# Redundant_Power_Supplies.net
KiCad netlist of a schematic drawn in Altium Designer
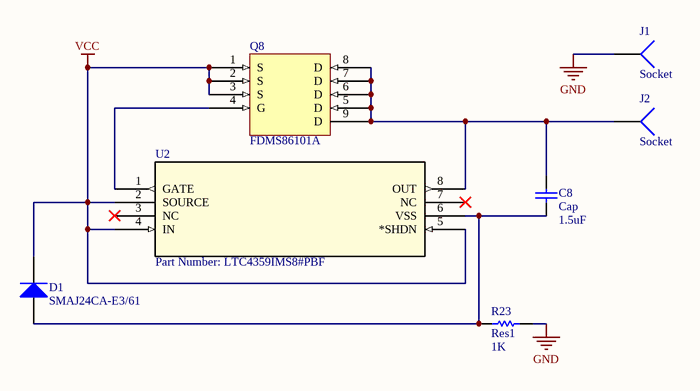
[diagram p0: Redundant Power Supplies.SchDoc]

(export (version "E")
  (design (tool "Eeschema 10.0.6"))
  (components
    (comp (ref "C8")
      (value "Cap")
      (footprint "C2012X7R1A155K:CAP_2012")
      (description "Capacitor")
      (fields (field (name "ALTIUM_VALUE") "1.5uF") (field (name "PUBLISHER") "Altium Limited"))
      (libsource (lib "Miscellaneous Devices") (part "Cap"))
    )
    (comp (ref "D1")
      (value "SMAJ24CA-E3/61")
      (footprint "SMAJ24CA-E361:DIODE_DO-214AC")
      (description "Default Diode")
      (fields (field (name "PUBLISHER") "Altium Limited"))
      (libsource (lib "Miscellaneous Devices") (part "Diode"))
    )
    (comp (ref "J1")
      (value "Socket")
      (footprint "SMD Power Pad:PCBComponent_1")
      (fields (field (name "PUBLISHER") "Altium Limited"))
      (libsource (lib "Miscellaneous Connectors") (part "Socket"))
    )
    (comp (ref "J2")
      (value "Socket")
      (footprint "SMD Power Pad:PCBComponent_1")
      (fields (field (name "PUBLISHER") "Altium Limited"))
      (libsource (lib "Miscellaneous Connectors") (part "Socket"))
    )
    (comp (ref "Q8")
      (value "FDMS86101A")
      (footprint "FDMS86101A:FDMS86101A")
      (description "MOSFET N-CH 100V 13A POWER56")
      (libsource (lib "FDMS86101A") (part "FDMS86101A"))
    )
    (comp (ref "R23")
      (value "Res1")
      (footprint "RMCF2512JT1K00:STA_RMCF2512")
      (description "Resistor")
      (fields (field (name "ALTIUM_VALUE") "1K") (field (name "PUBLISHER") "Altium Limited"))
      (libsource (lib "Miscellaneous Devices") (part "Res1"))
    )
    (comp (ref "U2")
      (value "Part Number: LTC4359IMS8#PBF")
      (footprint "MSOP-8_MS")
      (description "No Description Available")
      (fields
        (field (name "MANUFACTURER_PART_NUMBER") "LTC4359IMS8#PBF")
        (field (name "COPYRIGHT") "Copyright (C) 2018 Accelerated Designs. All rights reserved")
      )
      (libsource (lib "LTC4359IMS8#PBF") (part "LTC4359IMS8#PBF"))
    )
  )
  (nets
    (net (code "1") (name "GND") (class "Default")
      (node (ref "J1") (pin "1") (pinfunction "1_1") (pintype "passive"))
      (node (ref "R23") (pin "2") (pinfunction "2_2") (pintype "passive"))
    )
    (net (code "2") (name "Net-(D1-A)") (class "Default")
      (node (ref "C8") (pin "1") (pinfunction "1_1") (pintype "passive"))
      (node (ref "D1") (pin "1") (pinfunction "A_1") (pintype "passive"))
      (node (ref "R23") (pin "1") (pinfunction "1_1") (pintype "passive"))
      (node (ref "U2") (pin "6") (pinfunction "VSS_6") (pintype "power_in"))
    )
    (net (code "3") (name "Net-(Q8-G)") (class "Default")
      (node (ref "Q8") (pin "4") (pinfunction "G_4") (pintype "input"))
      (node (ref "U2") (pin "1") (pinfunction "GATE_1") (pintype "output"))
    )
    (net (code "4") (name "Net-(U2-OUT)") (class "Default")
      (node (ref "C8") (pin "2") (pinfunction "2_2") (pintype "passive"))
      (node (ref "J2") (pin "1") (pinfunction "1_1") (pintype "passive"))
      (node (ref "Q8") (pin "5") (pinfunction "D_5") (pintype "input"))
      (node (ref "Q8") (pin "6") (pinfunction "D_6") (pintype "input"))
      (node (ref "Q8") (pin "7") (pinfunction "D_7") (pintype "input"))
      (node (ref "Q8") (pin "8") (pinfunction "D_8") (pintype "input"))
      (node (ref "Q8") (pin "9") (pinfunction "D_9") (pintype "passive"))
      (node (ref "U2") (pin "8") (pinfunction "OUT_8") (pintype "output"))
    )
    (net (code "5") (name "VCC") (class "Default")
      (node (ref "D1") (pin "2") (pinfunction "K_2") (pintype "passive"))
      (node (ref "Q8") (pin "1") (pinfunction "S_1") (pintype "input"))
      (node (ref "Q8") (pin "2") (pinfunction "S_2") (pintype "input"))
      (node (ref "Q8") (pin "3") (pinfunction "S_3") (pintype "input"))
      (node (ref "U2") (pin "2") (pinfunction "SOURCE_2") (pintype "passive"))
      (node (ref "U2") (pin "4") (pinfunction "IN_4") (pintype "input"))
      (node (ref "U2") (pin "5") (pinfunction "*SHDN_5") (pintype "input"))
    )
    (net (code "6") (name "unconnected-(U2-NC-Pad3)") (class "Default")
      (node (ref "U2") (pin "3") (pinfunction "NC_3") (pintype "passive+no_connect"))
    )
    (net (code "7") (name "unconnected-(U2-NC-Pad7)") (class "Default")
      (node (ref "U2") (pin "7") (pinfunction "NC_7") (pintype "passive+no_connect"))
    )
  )
)
